# EPS_Temperature-Sensor.net
KiCad netlist of a schematic drawn in Altium Designer
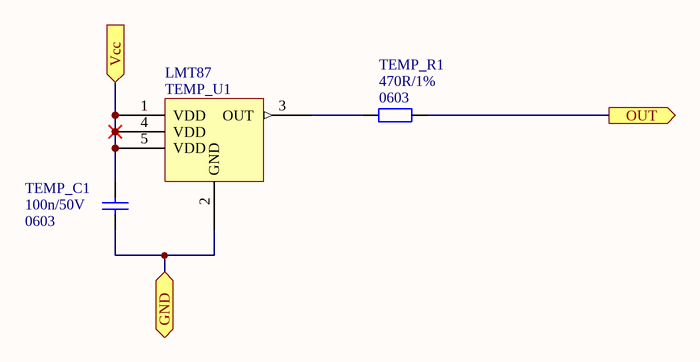
[diagram p0: EPS_Temperature-Sensor.SchDoc]

(export (version "E")
  (design (tool "Eeschema 10.0.6"))
  (components
    (comp (ref "TEMP_C1")
      (value "100n/50V")
      (footprint "SMD_Capacitor_0603")
      (description "Ceramic Cap Kemet COTS 100n/50V X7R 0603")
      (fields
        (field (name "MANUFACTURER") "Kemet")
        (field (name "MANUFACTURERPARTNUMBER") "C0603T104K5RALTU")
        (field (name "PACKAGE") "0603")
      )
      (libsource (lib "capacitors") (part "Cer_C0603T104K5RALTU"))
    )
    (comp (ref "TEMP_R1")
      (value "470R/1%")
      (footprint "SMD_Resistor_0603")
      (description "1k/1% Vishay CRCW 0603 Resistor. 100mW, 100ppm, 75V.")
      (fields
        (field (name "MANUFACTURER") "Vishay")
        (field (name "MANUFACTURERPARTNUMBER") "CRCW06031K00FKxxxx")
        (field (name "PACKAGE") "0603")
      )
      (libsource (lib "resistors") (part "CRCW06031K00FKxxxx"))
    )
    (comp (ref "TEMP_U1")
      (value "LMT87")
      (footprint "SC70-LT5_N")
      (description "Analog Temperature Sensors with Class-AB Output")
      (libsource (lib "microcircuits") (part "LMT87"))
    )
  )
  (nets
    (net (code "1") (name "/GND") (class "Default")
      (node (ref "TEMP_C1") (pin "2") (pinfunction "2_2") (pintype "passive"))
      (node (ref "TEMP_U1") (pin "2") (pinfunction "GND_2") (pintype "power_in"))
    )
    (net (code "2") (name "/OUT") (class "Default")
      (node (ref "TEMP_R1") (pin "2") (pinfunction "2_2") (pintype "passive"))
    )
    (net (code "3") (name "/Vcc") (class "Default")
      (node (ref "TEMP_C1") (pin "1") (pinfunction "1_1") (pintype "passive"))
      (node (ref "TEMP_U1") (pin "1") (pinfunction "VDD_1") (pintype "passive"))
      (node (ref "TEMP_U1") (pin "4") (pinfunction "VDD_4") (pintype "power_in"))
      (node (ref "TEMP_U1") (pin "5") (pinfunction "VDD_5") (pintype "power_in"))
    )
    (net (code "4") (name "Net-(TEMP_U1-OUT)") (class "Default")
      (node (ref "TEMP_R1") (pin "1") (pinfunction "1_1") (pintype "passive"))
      (node (ref "TEMP_U1") (pin "3") (pinfunction "OUT_3") (pintype "output"))
    )
  )
)
